# extruderControllerv02.net
KiCad netlist of a schematic drawn in EAGLE
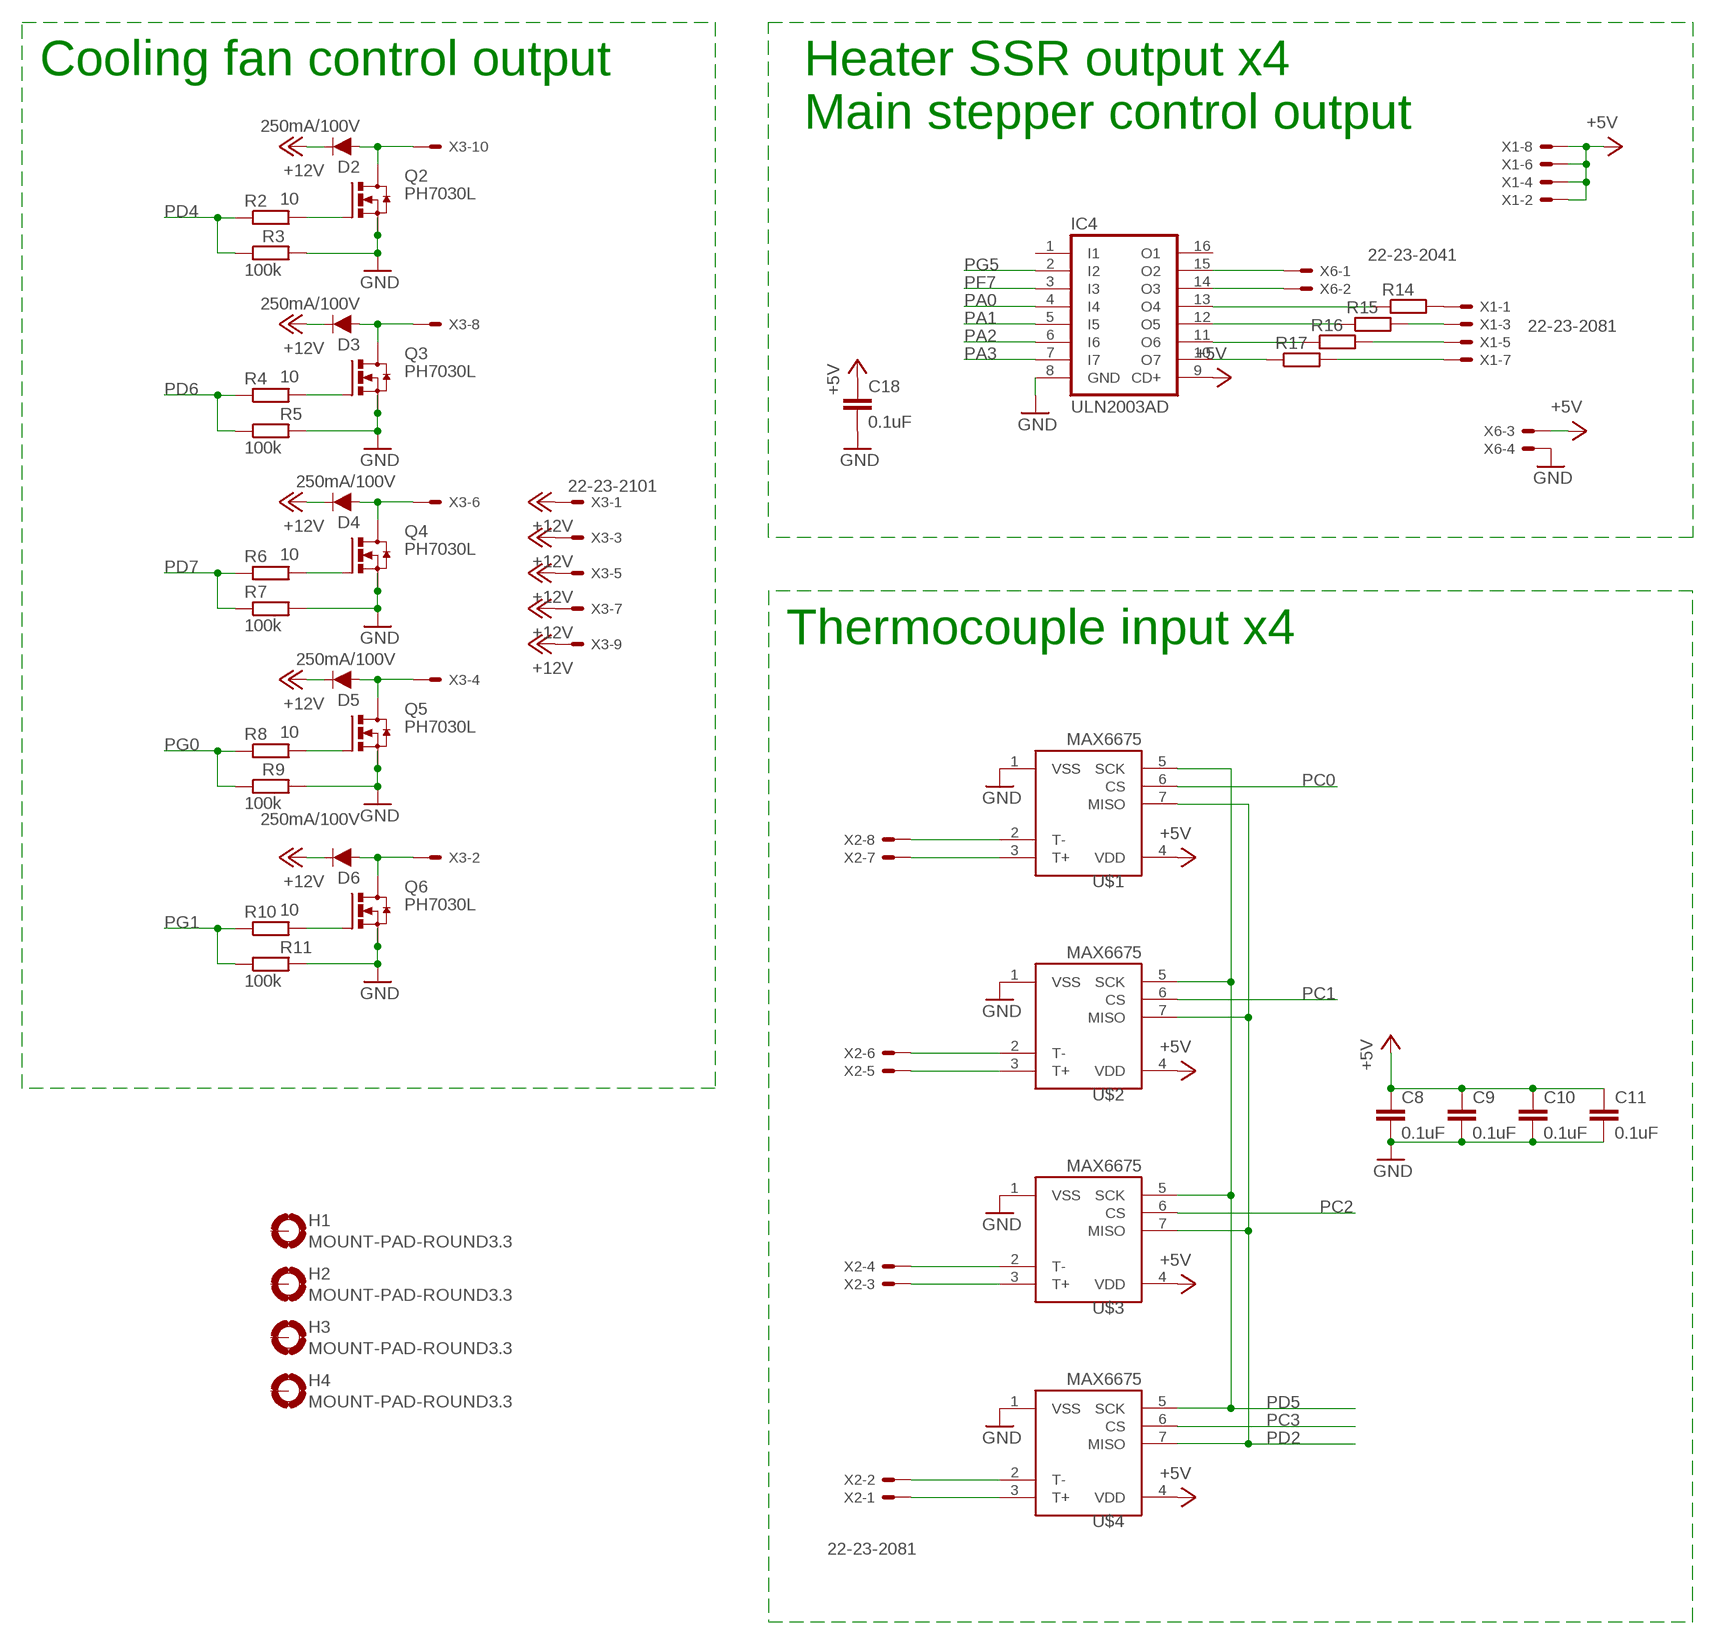
[diagram p0: schematic, sheet 1, part 1 of 2]
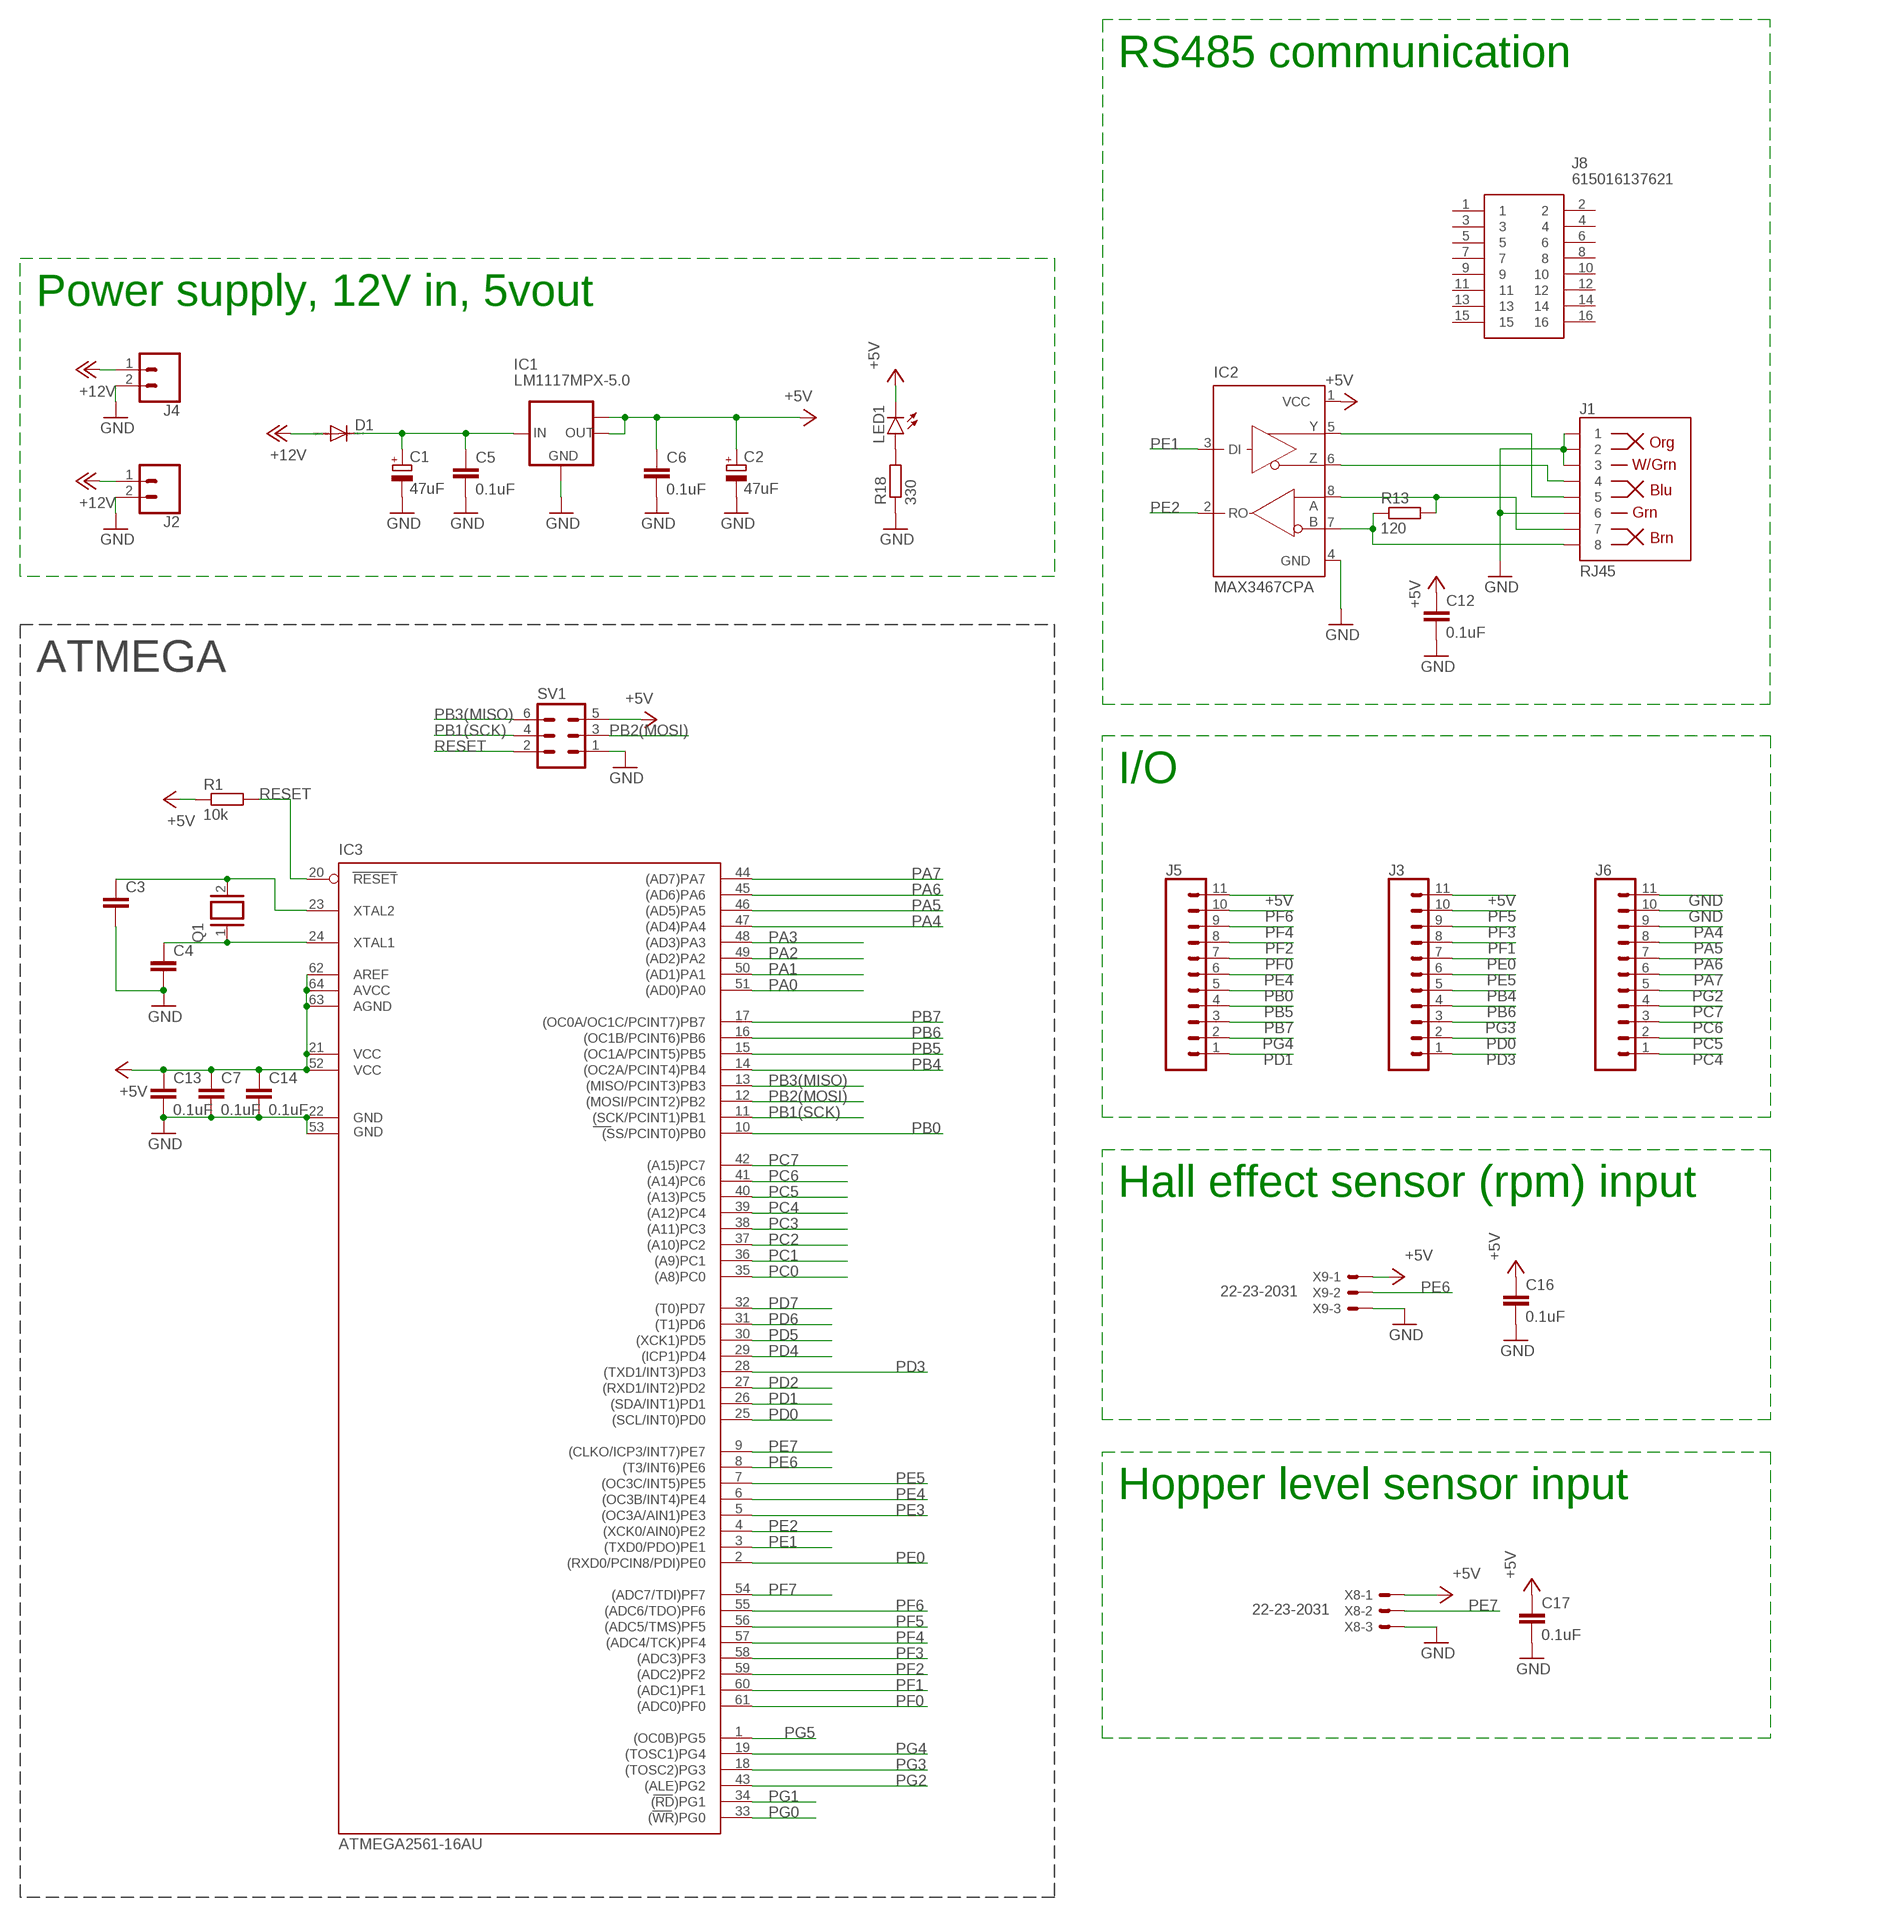
[diagram p1: schematic, sheet 1, part 2 of 2]

(export (version "E")
  (design (tool "Eeschema 10.0.6"))
  (components
    (comp (ref "C1")
      (value "47uF")
      (footprint "eagle-import:PANASONIC_D")
      (libsource (lib "eagle-import") (part "CPOL-EUD"))
    )
    (comp (ref "C2")
      (value "47uF")
      (footprint "eagle-import:PANASONIC_D")
      (libsource (lib "eagle-import") (part "CPOL-EUD"))
    )
    (comp (ref "C3")
      (value "C-EUC0603")
      (footprint "eagle-import:C0603")
      (libsource (lib "eagle-import") (part "C-EUC0603"))
    )
    (comp (ref "C4")
      (value "C-EUC0603")
      (footprint "eagle-import:C0603")
      (libsource (lib "eagle-import") (part "C-EUC0603"))
    )
    (comp (ref "C5")
      (value "0.1uF")
      (footprint "eagle-import:C0603")
      (libsource (lib "eagle-import") (part "C-EUC0603"))
    )
    (comp (ref "C6")
      (value "0.1uF")
      (footprint "eagle-import:C0603")
      (libsource (lib "eagle-import") (part "C-EUC0603"))
    )
    (comp (ref "C7")
      (value "0.1uF")
      (footprint "eagle-import:C0603")
      (libsource (lib "eagle-import") (part "C-EUC0603"))
    )
    (comp (ref "C8")
      (value "0.1uF")
      (footprint "eagle-import:C0603")
      (libsource (lib "eagle-import") (part "C-EUC0603"))
    )
    (comp (ref "C9")
      (value "0.1uF")
      (footprint "eagle-import:C0603")
      (libsource (lib "eagle-import") (part "C-EUC0603"))
    )
    (comp (ref "C10")
      (value "0.1uF")
      (footprint "eagle-import:C0603")
      (libsource (lib "eagle-import") (part "C-EUC0603"))
    )
    (comp (ref "C11")
      (value "0.1uF")
      (footprint "eagle-import:C0603")
      (libsource (lib "eagle-import") (part "C-EUC0603"))
    )
    (comp (ref "C12")
      (value "0.1uF")
      (footprint "eagle-import:C0603")
      (libsource (lib "eagle-import") (part "C-EUC0603"))
    )
    (comp (ref "C13")
      (value "0.1uF")
      (footprint "eagle-import:C0603")
      (libsource (lib "eagle-import") (part "C-EUC0603"))
    )
    (comp (ref "C14")
      (value "0.1uF")
      (footprint "eagle-import:C0603")
      (libsource (lib "eagle-import") (part "C-EUC0603"))
    )
    (comp (ref "C16")
      (value "0.1uF")
      (footprint "eagle-import:C0603")
      (libsource (lib "eagle-import") (part "C-EUC0603"))
    )
    (comp (ref "C17")
      (value "0.1uF")
      (footprint "eagle-import:C0603")
      (libsource (lib "eagle-import") (part "C-EUC0603"))
    )
    (comp (ref "C18")
      (value "0.1uF")
      (footprint "eagle-import:C0603")
      (libsource (lib "eagle-import") (part "C-EUC0603"))
    )
    (comp (ref "D1")
      (value "DIODE-SMB")
      (footprint "eagle-import:SMB")
      (libsource (lib "eagle-import") (part "DIODE-SMB"))
    )
    (comp (ref "D2")
      (value "250mA/100V")
      (footprint "eagle-import:SOD-323")
      (libsource (lib "eagle-import") (part "DIODE-BAS16J"))
    )
    (comp (ref "D3")
      (value "250mA/100V")
      (footprint "eagle-import:SOD-323")
      (libsource (lib "eagle-import") (part "DIODE-BAS16J"))
    )
    (comp (ref "D4")
      (value "250mA/100V")
      (footprint "eagle-import:SOD-323")
      (libsource (lib "eagle-import") (part "DIODE-BAS16J"))
    )
    (comp (ref "D5")
      (value "250mA/100V")
      (footprint "eagle-import:SOD-323")
      (libsource (lib "eagle-import") (part "DIODE-BAS16J"))
    )
    (comp (ref "D6")
      (value "250mA/100V")
      (footprint "eagle-import:SOD-323")
      (libsource (lib "eagle-import") (part "DIODE-BAS16J"))
    )
    (comp (ref "H1")
      (value "MOUNT-PAD-ROUND3.3")
      (footprint "eagle-import:3,3-PAD")
      (libsource (lib "eagle-import") (part "MOUNT-PAD-ROUND3.3"))
    )
    (comp (ref "H2")
      (value "MOUNT-PAD-ROUND3.3")
      (footprint "eagle-import:3,3-PAD")
      (libsource (lib "eagle-import") (part "MOUNT-PAD-ROUND3.3"))
    )
    (comp (ref "H3")
      (value "MOUNT-PAD-ROUND3.3")
      (footprint "eagle-import:3,3-PAD")
      (libsource (lib "eagle-import") (part "MOUNT-PAD-ROUND3.3"))
    )
    (comp (ref "H4")
      (value "MOUNT-PAD-ROUND3.3")
      (footprint "eagle-import:3,3-PAD")
      (libsource (lib "eagle-import") (part "MOUNT-PAD-ROUND3.3"))
    )
    (comp (ref "IC1")
      (value "LM1117MPX-5.0")
      (footprint "eagle-import:SOT223")
      (libsource (lib "eagle-import") (part "LM1117MPX-5.0"))
    )
    (comp (ref "IC2")
      (value "MAX3467CPA")
      (footprint "eagle-import:SO08")
      (libsource (lib "eagle-import") (part "MAX3467PAC"))
    )
    (comp (ref "IC3")
      (value "ATMEGA2561-16AU")
      (footprint "eagle-import:TQFP64")
      (libsource (lib "eagle-import") (part "ATMEGA2561AU-16"))
    )
    (comp (ref "IC4")
      (value "ULN2003AD")
      (footprint "eagle-import:SO16")
      (libsource (lib "eagle-import") (part "ULN2003AD"))
    )
    (comp (ref "J1")
      (value "RJ45")
      (footprint "eagle-import:RJ45-8")
      (libsource (lib "eagle-import") (part "RJ45-8"))
    )
    (comp (ref "J2")
      (value "CONN_023.5MM")
      (footprint "eagle-import:SCREWTERMINAL-3.5MM-2")
      (libsource (lib "eagle-import") (part "CONN_023.5MM"))
    )
    (comp (ref "J3")
      (value "CONN_11")
      (footprint "eagle-import:1X11")
      (libsource (lib "eagle-import") (part "CONN_11"))
    )
    (comp (ref "J4")
      (value "CONN_023.5MM")
      (footprint "eagle-import:SCREWTERMINAL-3.5MM-2")
      (libsource (lib "eagle-import") (part "CONN_023.5MM"))
    )
    (comp (ref "J5")
      (value "CONN_11")
      (footprint "eagle-import:1X11")
      (libsource (lib "eagle-import") (part "CONN_11"))
    )
    (comp (ref "J6")
      (value "CONN_11")
      (footprint "eagle-import:1X11")
      (libsource (lib "eagle-import") (part "CONN_11"))
    )
    (comp (ref "J8")
      (value "615016137621")
      (footprint "eagle-import:WR-MJ")
      (fields (field (name "MOUSER_PART_NUMBER") "710-615016137621"))
      (libsource (lib "eagle-import") (part "615016137621"))
    )
    (comp (ref "LED1")
      (value "LEDSML1206")
      (footprint "eagle-import:SML1206")
      (libsource (lib "eagle-import") (part "LEDSML1206"))
    )
    (comp (ref "Q1")
      (value "XTAL/S")
      (footprint "eagle-import:QS")
      (fields (field (name "SPICEPREFIX") "B"))
      (libsource (lib "eagle-import") (part "XTAL/S"))
    )
    (comp (ref "Q2")
      (value "PH7030L")
      (footprint "eagle-import:SOT669")
      (libsource (lib "eagle-import") (part "PH7030L"))
    )
    (comp (ref "Q3")
      (value "PH7030L")
      (footprint "eagle-import:SOT669")
      (libsource (lib "eagle-import") (part "PH7030L"))
    )
    (comp (ref "Q4")
      (value "PH7030L")
      (footprint "eagle-import:SOT669")
      (libsource (lib "eagle-import") (part "PH7030L"))
    )
    (comp (ref "Q5")
      (value "PH7030L")
      (footprint "eagle-import:SOT669")
      (libsource (lib "eagle-import") (part "PH7030L"))
    )
    (comp (ref "Q6")
      (value "PH7030L")
      (footprint "eagle-import:SOT669")
      (libsource (lib "eagle-import") (part "PH7030L"))
    )
    (comp (ref "R1")
      (value "10k")
      (footprint "eagle-import:R0805")
      (libsource (lib "eagle-import") (part "R-EU_R0805"))
    )
    (comp (ref "R2")
      (value "10")
      (footprint "eagle-import:R0805")
      (libsource (lib "eagle-import") (part "R-EU_R0805"))
    )
    (comp (ref "R3")
      (value "100k")
      (footprint "eagle-import:R0805")
      (libsource (lib "eagle-import") (part "R-EU_R0805"))
    )
    (comp (ref "R4")
      (value "10")
      (footprint "eagle-import:R0805")
      (libsource (lib "eagle-import") (part "R-EU_R0805"))
    )
    (comp (ref "R5")
      (value "100k")
      (footprint "eagle-import:R0805")
      (libsource (lib "eagle-import") (part "R-EU_R0805"))
    )
    (comp (ref "R6")
      (value "10")
      (footprint "eagle-import:R0805")
      (libsource (lib "eagle-import") (part "R-EU_R0805"))
    )
    (comp (ref "R7")
      (value "100k")
      (footprint "eagle-import:R0805")
      (libsource (lib "eagle-import") (part "R-EU_R0805"))
    )
    (comp (ref "R8")
      (value "10")
      (footprint "eagle-import:R0805")
      (libsource (lib "eagle-import") (part "R-EU_R0805"))
    )
    (comp (ref "R9")
      (value "100k")
      (footprint "eagle-import:R0805")
      (libsource (lib "eagle-import") (part "R-EU_R0805"))
    )
    (comp (ref "R10")
      (value "10")
      (footprint "eagle-import:R0805")
      (libsource (lib "eagle-import") (part "R-EU_R0805"))
    )
    (comp (ref "R11")
      (value "100k")
      (footprint "eagle-import:R0805")
      (libsource (lib "eagle-import") (part "R-EU_R0805"))
    )
    (comp (ref "R13")
      (value "120")
      (footprint "eagle-import:R1210")
      (libsource (lib "eagle-import") (part "R-EU_R1210"))
    )
    (comp (ref "R14")
      (value "R-EU_R0805")
      (footprint "eagle-import:R0805")
      (libsource (lib "eagle-import") (part "R-EU_R0805"))
    )
    (comp (ref "R15")
      (value "R-EU_R0805")
      (footprint "eagle-import:R0805")
      (libsource (lib "eagle-import") (part "R-EU_R0805"))
    )
    (comp (ref "R16")
      (value "R-EU_R0805")
      (footprint "eagle-import:R0805")
      (libsource (lib "eagle-import") (part "R-EU_R0805"))
    )
    (comp (ref "R17")
      (value "R-EU_R0805")
      (footprint "eagle-import:R0805")
      (libsource (lib "eagle-import") (part "R-EU_R0805"))
    )
    (comp (ref "R18")
      (value "330")
      (footprint "eagle-import:R0805")
      (libsource (lib "eagle-import") (part "R-EU_R0805"))
    )
    (comp (ref "SV1")
      (value "MA03-2")
      (footprint "eagle-import:MA03-2")
      (libsource (lib "eagle-import") (part "MA03-2"))
    )
    (comp (ref "U$1")
      (value "MAX6675")
      (footprint "eagle-import:SO08-MAX6675")
      (libsource (lib "eagle-import") (part "MAX6675"))
    )
    (comp (ref "U$2")
      (value "MAX6675")
      (footprint "eagle-import:SO08-MAX6675")
      (libsource (lib "eagle-import") (part "MAX6675"))
    )
    (comp (ref "U$3")
      (value "MAX6675")
      (footprint "eagle-import:SO08-MAX6675")
      (libsource (lib "eagle-import") (part "MAX6675"))
    )
    (comp (ref "U$4")
      (value "MAX6675")
      (footprint "eagle-import:SO08-MAX6675")
      (libsource (lib "eagle-import") (part "MAX6675"))
    )
    (comp (ref "X1")
      (value "22-23-2081")
      (footprint "eagle-import:22-23-2081")
      (fields (field (name "MF") "MOLEX"))
      (libsource (lib "eagle-import") (part "22-23-2081"))
    )
    (comp (ref "X2")
      (value "22-23-2081")
      (footprint "eagle-import:22-23-2081")
      (fields (field (name "MF") "MOLEX"))
      (libsource (lib "eagle-import") (part "22-23-2081"))
    )
    (comp (ref "X3")
      (value "22-23-2101")
      (footprint "eagle-import:22-23-2101")
      (fields (field (name "MF") "MOLEX"))
      (libsource (lib "eagle-import") (part "22-23-2101"))
    )
    (comp (ref "X6")
      (value "22-23-2041")
      (footprint "eagle-import:22-23-2041")
      (fields (field (name "MF") "MOLEX"))
      (libsource (lib "eagle-import") (part "22-23-2041"))
    )
    (comp (ref "X8")
      (value "22-23-2031")
      (footprint "eagle-import:22-23-2031")
      (fields (field (name "MF") "MOLEX"))
      (libsource (lib "eagle-import") (part "22-23-2031"))
    )
    (comp (ref "X9")
      (value "22-23-2031")
      (footprint "eagle-import:22-23-2031")
      (fields (field (name "MF") "MOLEX"))
      (libsource (lib "eagle-import") (part "22-23-2031"))
    )
  )
  (nets
    (net (code "1") (name "+5V") (class "Default")
      (node (ref "C10") (pin "1") (pinfunction "1_1") (pintype "passive"))
      (node (ref "C11") (pin "1") (pinfunction "1_1") (pintype "passive"))
      (node (ref "C12") (pin "1") (pinfunction "1_1") (pintype "passive"))
      (node (ref "C13") (pin "1") (pinfunction "1_1") (pintype "passive"))
      (node (ref "C14") (pin "1") (pinfunction "1_1") (pintype "passive"))
      (node (ref "C16") (pin "1") (pinfunction "1_1") (pintype "passive"))
      (node (ref "C17") (pin "1") (pinfunction "1_1") (pintype "passive"))
      (node (ref "C18") (pin "1") (pinfunction "1_1") (pintype "passive"))
      (node (ref "C2") (pin "+") (pinfunction "+_+") (pintype "passive"))
      (node (ref "C6") (pin "1") (pinfunction "1_1") (pintype "passive"))
      (node (ref "C7") (pin "1") (pinfunction "1_1") (pintype "passive"))
      (node (ref "C8") (pin "1") (pinfunction "1_1") (pintype "passive"))
      (node (ref "C9") (pin "1") (pinfunction "1_1") (pintype "passive"))
      (node (ref "IC1") (pin "2") (pinfunction "OUT_2") (pintype "passive"))
      (node (ref "IC1") (pin "TAB") (pinfunction "OUT1_TAB") (pintype "passive"))
      (node (ref "IC2") (pin "1") (pinfunction "VCC_1") (pintype "power_in"))
      (node (ref "IC3") (pin "21") (pinfunction "VCC_21") (pintype "power_in"))
      (node (ref "IC3") (pin "52") (pinfunction "VCC1_52") (pintype "power_in"))
      (node (ref "IC3") (pin "62") (pinfunction "AREF_62") (pintype "bidirectional"))
      (node (ref "IC3") (pin "63") (pinfunction "AGND_63") (pintype "power_in"))
      (node (ref "IC3") (pin "64") (pinfunction "AVCC_64") (pintype "power_in"))
      (node (ref "IC4") (pin "9") (pinfunction "CD+_9") (pintype "passive"))
      (node (ref "J3") (pin "11") (pinfunction "11_11") (pintype "passive"))
      (node (ref "J5") (pin "11") (pinfunction "11_11") (pintype "passive"))
      (node (ref "LED1") (pin "C") (pinfunction "C_C") (pintype "passive"))
      (node (ref "R1") (pin "1") (pinfunction "1_1") (pintype "passive"))
      (node (ref "SV1") (pin "5") (pinfunction "5_5") (pintype "passive"))
      (node (ref "U$1") (pin "4") (pinfunction "VDD_4") (pintype "bidirectional"))
      (node (ref "U$2") (pin "4") (pinfunction "VDD_4") (pintype "bidirectional"))
      (node (ref "U$3") (pin "4") (pinfunction "VDD_4") (pintype "bidirectional"))
      (node (ref "U$4") (pin "4") (pinfunction "VDD_4") (pintype "bidirectional"))
      (node (ref "X1") (pin "2") (pinfunction "S_2") (pintype "passive"))
      (node (ref "X1") (pin "4") (pinfunction "S_4") (pintype "passive"))
      (node (ref "X1") (pin "6") (pinfunction "S_6") (pintype "passive"))
      (node (ref "X1") (pin "8") (pinfunction "S_8") (pintype "passive"))
      (node (ref "X6") (pin "3") (pinfunction "S_3") (pintype "passive"))
      (node (ref "X8") (pin "1") (pinfunction "S_1") (pintype "passive"))
      (node (ref "X9") (pin "1") (pinfunction "S_1") (pintype "passive"))
    )
    (net (code "2") (name "+12V") (class "Default")
      (node (ref "D1") (pin "A") (pinfunction "A_A") (pintype "passive"))
      (node (ref "D2") (pin "C") (pinfunction "C_C") (pintype "passive"))
      (node (ref "D3") (pin "C") (pinfunction "C_C") (pintype "passive"))
      (node (ref "D4") (pin "C") (pinfunction "C_C") (pintype "passive"))
      (node (ref "D5") (pin "C") (pinfunction "C_C") (pintype "passive"))
      (node (ref "D6") (pin "C") (pinfunction "C_C") (pintype "passive"))
      (node (ref "J2") (pin "1") (pinfunction "1_1") (pintype "passive"))
      (node (ref "J4") (pin "1") (pinfunction "1_1") (pintype "passive"))
      (node (ref "X3") (pin "1") (pinfunction "S_1") (pintype "passive"))
      (node (ref "X3") (pin "3") (pinfunction "S_3") (pintype "passive"))
      (node (ref "X3") (pin "5") (pinfunction "S_5") (pintype "passive"))
      (node (ref "X3") (pin "7") (pinfunction "S_7") (pintype "passive"))
      (node (ref "X3") (pin "9") (pinfunction "S_9") (pintype "passive"))
    )
    (net (code "3") (name "/PA0") (class "Default")
      (node (ref "IC3") (pin "51") (pinfunction "(AD0)PA0_51") (pintype "bidirectional"))
      (node (ref "IC4") (pin "4") (pinfunction "I4_4") (pintype "input"))
    )
    (net (code "4") (name "/PA1") (class "Default")
      (node (ref "IC3") (pin "50") (pinfunction "(AD1)PA1_50") (pintype "bidirectional"))
      (node (ref "IC4") (pin "5") (pinfunction "I5_5") (pintype "input"))
    )
    (net (code "5") (name "/PA2") (class "Default")
      (node (ref "IC3") (pin "49") (pinfunction "(AD2)PA2_49") (pintype "bidirectional"))
      (node (ref "IC4") (pin "6") (pinfunction "I6_6") (pintype "input"))
    )
    (net (code "6") (name "/PA3") (class "Default")
      (node (ref "IC3") (pin "48") (pinfunction "(AD3)PA3_48") (pintype "bidirectional"))
      (node (ref "IC4") (pin "7") (pinfunction "I7_7") (pintype "input"))
    )
    (net (code "7") (name "/PA4") (class "Default")
      (node (ref "IC3") (pin "47") (pinfunction "(AD4)PA4_47") (pintype "bidirectional"))
      (node (ref "J6") (pin "9") (pinfunction "9_9") (pintype "passive"))
    )
    (net (code "8") (name "/PA5") (class "Default")
      (node (ref "IC3") (pin "46") (pinfunction "(AD5)PA5_46") (pintype "bidirectional"))
      (node (ref "J6") (pin "8") (pinfunction "8_8") (pintype "passive"))
    )
    (net (code "9") (name "/PA6") (class "Default")
      (node (ref "IC3") (pin "45") (pinfunction "(AD6)PA6_45") (pintype "bidirectional"))
      (node (ref "J6") (pin "7") (pinfunction "7_7") (pintype "passive"))
    )
    (net (code "10") (name "/PA7") (class "Default")
      (node (ref "IC3") (pin "44") (pinfunction "(AD7)PA7_44") (pintype "bidirectional"))
      (node (ref "J6") (pin "6") (pinfunction "6_6") (pintype "passive"))
    )
    (net (code "11") (name "/PB0") (class "Default")
      (node (ref "IC3") (pin "10") (pinfunction "(SS/PCINT0)PB0_10") (pintype "bidirectional"))
      (node (ref "J5") (pin "5") (pinfunction "5_5") (pintype "passive"))
    )
    (net (code "12") (name "/PB1(SCK)") (class "Default")
      (node (ref "IC3") (pin "11") (pinfunction "(SCK/PCINT1)PB1_11") (pintype "bidirectional"))
      (node (ref "SV1") (pin "4") (pinfunction "4_4") (pintype "passive"))
    )
    (net (code "13") (name "/PB2(MOSI)") (class "Default")
      (node (ref "IC3") (pin "12") (pinfunction "(MOSI/PCINT2)PB2_12") (pintype "bidirectional"))
      (node (ref "SV1") (pin "3") (pinfunction "3_3") (pintype "passive"))
    )
    (net (code "14") (name "/PB3(MISO)") (class "Default")
      (node (ref "IC3") (pin "13") (pinfunction "(MISO/PCINT3)PB3_13") (pintype "bidirectional"))
      (node (ref "SV1") (pin "6") (pinfunction "6_6") (pintype "passive"))
    )
    (net (code "15") (name "/PB4") (class "Default")
      (node (ref "IC3") (pin "14") (pinfunction "(OC2A/PCINT4)PB4_14") (pintype "bidirectional"))
      (node (ref "J3") (pin "5") (pinfunction "5_5") (pintype "passive"))
    )
    (net (code "16") (name "/PB5") (class "Default")
      (node (ref "IC3") (pin "15") (pinfunction "(OC1A/PCINT5)PB5_15") (pintype "bidirectional"))
      (node (ref "J5") (pin "4") (pinfunction "4_4") (pintype "passive"))
    )
    (net (code "17") (name "/PB6") (class "Default")
      (node (ref "IC3") (pin "16") (pinfunction "(OC1B/PCINT6)PB6_16") (pintype "bidirectional"))
      (node (ref "J3") (pin "4") (pinfunction "4_4") (pintype "passive"))
    )
    (net (code "18") (name "/PB7") (class "Default")
      (node (ref "IC3") (pin "17") (pinfunction "(OC0A/OC1C/PCINT7)PB7_17") (pintype "bidirectional"))
      (node (ref "J5") (pin "3") (pinfunction "3_3") (pintype "passive"))
    )
    (net (code "19") (name "/PC0") (class "Default")
      (node (ref "IC3") (pin "35") (pinfunction "(A8)PC0_35") (pintype "bidirectional"))
      (node (ref "U$1") (pin "6") (pinfunction "CS_6") (pintype "bidirectional"))
    )
    (net (code "20") (name "/PC1") (class "Default")
      (node (ref "IC3") (pin "36") (pinfunction "(A9)PC1_36") (pintype "bidirectional"))
      (node (ref "U$2") (pin "6") (pinfunction "CS_6") (pintype "bidirectional"))
    )
    (net (code "21") (name "/PC2") (class "Default")
      (node (ref "IC3") (pin "37") (pinfunction "(A10)PC2_37") (pintype "bidirectional"))
      (node (ref "U$3") (pin "6") (pinfunction "CS_6") (pintype "bidirectional"))
    )
    (net (code "22") (name "/PC3") (class "Default")
      (node (ref "IC3") (pin "38") (pinfunction "(A11)PC3_38") (pintype "bidirectional"))
      (node (ref "U$4") (pin "6") (pinfunction "CS_6") (pintype "bidirectional"))
    )
    (net (code "23") (name "/PC4") (class "Default")
      (node (ref "IC3") (pin "39") (pinfunction "(A12)PC4_39") (pintype "bidirectional"))
      (node (ref "J6") (pin "1") (pinfunction "1_1") (pintype "passive"))
    )
    (net (code "24") (name "/PC5") (class "Default")
      (node (ref "IC3") (pin "40") (pinfunction "(A13)PC5_40") (pintype "bidirectional"))
      (node (ref "J6") (pin "2") (pinfunction "2_2") (pintype "passive"))
    )
    (net (code "25") (name "/PC6") (class "Default")
      (node (ref "IC3") (pin "41") (pinfunction "(A14)PC6_41") (pintype "bidirectional"))
      (node (ref "J6") (pin "3") (pinfunction "3_3") (pintype "passive"))
    )
    (net (code "26") (name "/PC7") (class "Default")
      (node (ref "IC3") (pin "42") (pinfunction "(A15)PC7_42") (pintype "bidirectional"))
      (node (ref "J6") (pin "4") (pinfunction "4_4") (pintype "passive"))
    )
    (net (code "27") (name "/PD0") (class "Default")
      (node (ref "IC3") (pin "25") (pinfunction "(SCL/INT0)PD0_25") (pintype "bidirectional"))
      (node (ref "J3") (pin "2") (pinfunction "2_2") (pintype "passive"))
    )
    (net (code "28") (name "/PD1") (class "Default")
      (node (ref "IC3") (pin "26") (pinfunction "(SDA/INT1)PD1_26") (pintype "bidirectional"))
      (node (ref "J5") (pin "1") (pinfunction "1_1") (pintype "passive"))
    )
    (net (code "29") (name "/PD2") (class "Default")
      (node (ref "IC3") (pin "27") (pinfunction "(RXD1/INT2)PD2_27") (pintype "bidirectional"))
      (node (ref "U$1") (pin "7") (pinfunction "MISO_7") (pintype "bidirectional"))
      (node (ref "U$2") (pin "7") (pinfunction "MISO_7") (pintype "bidirectional"))
      (node (ref "U$3") (pin "7") (pinfunction "MISO_7") (pintype "bidirectional"))
      (node (ref "U$4") (pin "7") (pinfunction "MISO_7") (pintype "bidirectional"))
    )
    (net (code "30") (name "/PD3") (class "Default")
      (node (ref "IC3") (pin "28") (pinfunction "(TXD1/INT3)PD3_28") (pintype "bidirectional"))
      (node (ref "J3") (pin "1") (pinfunction "1_1") (pintype "passive"))
    )
    (net (code "31") (name "/PD4") (class "Default")
      (node (ref "IC3") (pin "29") (pinfunction "(ICP1)PD4_29") (pintype "bidirectional"))
      (node (ref "R2") (pin "1") (pinfunction "1_1") (pintype "passive"))
      (node (ref "R3") (pin "1") (pinfunction "1_1") (pintype "passive"))
    )
    (net (code "32") (name "/PD5") (class "Default")
      (node (ref "IC3") (pin "30") (pinfunction "(XCK1)PD5_30") (pintype "bidirectional"))
      (node (ref "U$1") (pin "5") (pinfunction "SCK_5") (pintype "bidirectional"))
      (node (ref "U$2") (pin "5") (pinfunction "SCK_5") (pintype "bidirectional"))
      (node (ref "U$3") (pin "5") (pinfunction "SCK_5") (pintype "bidirectional"))
      (node (ref "U$4") (pin "5") (pinfunction "SCK_5") (pintype "bidirectional"))
    )
    (net (code "33") (name "/PD6") (class "Default")
      (node (ref "IC3") (pin "31") (pinfunction "(T1)PD6_31") (pintype "bidirectional"))
      (node (ref "R4") (pin "1") (pinfunction "1_1") (pintype "passive"))
      (node (ref "R5") (pin "1") (pinfunction "1_1") (pintype "passive"))
    )
    (net (code "34") (name "/PD7") (class "Default")
      (node (ref "IC3") (pin "32") (pinfunction "(T0)PD7_32") (pintype "bidirectional"))
      (node (ref "R6") (pin "1") (pinfunction "1_1") (pintype "passive"))
      (node (ref "R7") (pin "1") (pinfunction "1_1") (pintype "passive"))
    )
    (net (code "35") (name "/PE0") (class "Default")
      (node (ref "IC3") (pin "2") (pinfunction "(RXD0/PCIN8/PDI)PE0_2") (pintype "bidirectional"))
      (node (ref "J3") (pin "7") (pinfunction "7_7") (pintype "passive"))
    )
    (net (code "36") (name "/PE1") (class "Default")
      (node (ref "IC2") (pin "3") (pinfunction "DI_3") (pintype "input"))
      (node (ref "IC3") (pin "3") (pinfunction "(TXD0/PDO)PE1_3") (pintype "bidirectional"))
    )
    (net (code "37") (name "/PE2") (class "Default")
      (node (ref "IC2") (pin "2") (pinfunction "RO_2") (pintype "output"))
      (node (ref "IC3") (pin "4") (pinfunction "(XCK0/AIN0)PE2_4") (pintype "bidirectional"))
    )
    (net (code "38") (name "/PE3") (class "Default")
      (node (ref "IC3") (pin "5") (pinfunction "(OC3A/AIN1)PE3_5") (pintype "bidirectional"))
    )
    (net (code "39") (name "/PE4") (class "Default")
      (node (ref "IC3") (pin "6") (pinfunction "(OC3B/INT4)PE4_6") (pintype "bidirectional"))
      (node (ref "J5") (pin "6") (pinfunction "6_6") (pintype "passive"))
    )
    (net (code "40") (name "/PE5") (class "Default")
      (node (ref "IC3") (pin "7") (pinfunction "(OC3C/INT5)PE5_7") (pintype "bidirectional"))
      (node (ref "J3") (pin "6") (pinfunction "6_6") (pintype "passive"))
    )
    (net (code "41") (name "/PE6") (class "Default")
      (node (ref "IC3") (pin "8") (pinfunction "(T3/INT6)PE6_8") (pintype "bidirectional"))
      (node (ref "X9") (pin "2") (pinfunction "S_2") (pintype "passive"))
    )
    (net (code "42") (name "/PE7") (class "Default")
      (node (ref "IC3") (pin "9") (pinfunction "(CLKO/ICP3/INT7)PE7_9") (pintype "bidirectional"))
      (node (ref "X8") (pin "2") (pinfunction "S_2") (pintype "passive"))
    )
    (net (code "43") (name "/PF0") (class "Default")
      (node (ref "IC3") (pin "61") (pinfunction "(ADC0)PF0_61") (pintype "bidirectional"))
      (node (ref "J5") (pin "7") (pinfunction "7_7") (pintype "passive"))
    )
    (net (code "44") (name "/PF1") (class "Default")
      (node (ref "IC3") (pin "60") (pinfunction "(ADC1)PF1_60") (pintype "bidirectional"))
      (node (ref "J3") (pin "8") (pinfunction "8_8") (pintype "passive"))
    )
    (net (code "45") (name "/PF2") (class "Default")
      (node (ref "IC3") (pin "59") (pinfunction "(ADC2)PF2_59") (pintype "bidirectional"))
      (node (ref "J5") (pin "8") (pinfunction "8_8") (pintype "passive"))
    )
    (net (code "46") (name "/PF3") (class "Default")
      (node (ref "IC3") (pin "58") (pinfunction "(ADC3)PF3_58") (pintype "bidirectional"))
      (node (ref "J3") (pin "9") (pinfunction "9_9") (pintype "passive"))
    )
    (net (code "47") (name "/PF4") (class "Default")
      (node (ref "IC3") (pin "57") (pinfunction "(ADC4/TCK)PF4_57") (pintype "bidirectional"))
      (node (ref "J5") (pin "9") (pinfunction "9_9") (pintype "passive"))
    )
    (net (code "48") (name "/PF5") (class "Default")
      (node (ref "IC3") (pin "56") (pinfunction "(ADC5/TMS)PF5_56") (pintype "bidirectional"))
      (node (ref "J3") (pin "10") (pinfunction "10_10") (pintype "passive"))
    )
    (net (code "49") (name "/PF6") (class "Default")
      (node (ref "IC3") (pin "55") (pinfunction "(ADC6/TDO)PF6_55") (pintype "bidirectional"))
      (node (ref "J5") (pin "10") (pinfunction "10_10") (pintype "passive"))
    )
    (net (code "50") (name "/PF7") (class "Default")
      (node (ref "IC3") (pin "54") (pinfunction "(ADC7/TDI)PF7_54") (pintype "bidirectional"))
      (node (ref "IC4") (pin "3") (pinfunction "I3_3") (pintype "input"))
    )
    (net (code "51") (name "/PG0") (class "Default")
      (node (ref "IC3") (pin "33") (pinfunction "(WR)PG0_33") (pintype "bidirectional"))
      (node (ref "R8") (pin "1") (pinfunction "1_1") (pintype "passive"))
      (node (ref "R9") (pin "1") (pinfunction "1_1") (pintype "passive"))
    )
    (net (code "52") (name "/PG1") (class "Default")
      (node (ref "IC3") (pin "34") (pinfunction "(RD)PG1_34") (pintype "bidirectional"))
      (node (ref "R10") (pin "1") (pinfunction "1_1") (pintype "passive"))
      (node (ref "R11") (pin "1") (pinfunction "1_1") (pintype "passive"))
    )
    (net (code "53") (name "/PG2") (class "Default")
      (node (ref "IC3") (pin "43") (pinfunction "(ALE)PG2_43") (pintype "bidirectional"))
      (node (ref "J6") (pin "5") (pinfunction "5_5") (pintype "passive"))
    )
    (net (code "54") (name "/PG3") (class "Default")
      (node (ref "IC3") (pin "18") (pinfunction "(TOSC2)PG3_18") (pintype "bidirectional"))
      (node (ref "J3") (pin "3") (pinfunction "3_3") (pintype "passive"))
    )
    (net (code "55") (name "/PG4") (class "Default")
      (node (ref "IC3") (pin "19") (pinfunction "(TOSC1)PG4_19") (pintype "bidirectional"))
      (node (ref "J5") (pin "2") (pinfunction "2_2") (pintype "passive"))
    )
    (net (code "56") (name "/PG5") (class "Default")
      (node (ref "IC3") (pin "1") (pinfunction "(OC0B)PG5_1") (pintype "bidirectional"))
      (node (ref "IC4") (pin "2") (pinfunction "I2_2") (pintype "input"))
    )
    (net (code "57") (name "/RESET") (class "Default")
      (node (ref "IC3") (pin "20") (pinfunction "RESET_20") (pintype "input"))
      (node (ref "R1") (pin "2") (pinfunction "2_2") (pintype "passive"))
      (node (ref "SV1") (pin "2") (pinfunction "2_2") (pintype "passive"))
    )
    (net (code "58") (name "GND") (class "Default")
      (node (ref "C1") (pin "-") (pinfunction "-_-") (pintype "passive"))
      (node (ref "C10") (pin "2") (pinfunction "2_2") (pintype "passive"))
      (node (ref "C11") (pin "2") (pinfunction "2_2") (pintype "passive"))
      (node (ref "C12") (pin "2") (pinfunction "2_2") (pintype "passive"))
      (node (ref "C13") (pin "2") (pinfunction "2_2") (pintype "passive"))
      (node (ref "C14") (pin "2") (pinfunction "2_2") (pintype "passive"))
      (node (ref "C16") (pin "2") (pinfunction "2_2") (pintype "passive"))
      (node (ref "C17") (pin "2") (pinfunction "2_2") (pintype "passive"))
      (node (ref "C18") (pin "2") (pinfunction "2_2") (pintype "passive"))
      (node (ref "C2") (pin "-") (pinfunction "-_-") (pintype "passive"))
      (node (ref "C3") (pin "2") (pinfunction "2_2") (pintype "passive"))
      (node (ref "C4") (pin "2") (pinfunction "2_2") (pintype "passive"))
      (node (ref "C5") (pin "2") (pinfunction "2_2") (pintype "passive"))
      (node (ref "C6") (pin "2") (pinfunction "2_2") (pintype "passive"))
      (node (ref "C7") (pin "2") (pinfunction "2_2") (pintype "passive"))
      (node (ref "C8") (pin "2") (pinfunction "2_2") (pintype "passive"))
      (node (ref "C9") (pin "2") (pinfunction "2_2") (pintype "passive"))
      (node (ref "IC1") (pin "1") (pinfunction "GND_1") (pintype "input"))
      (node (ref "IC2") (pin "4") (pinfunction "GND_4") (pintype "power_in"))
      (node (ref "IC3") (pin "22") (pinfunction "GND_22") (pintype "power_in"))
      (node (ref "IC3") (pin "53") (pinfunction "GND1_53") (pintype "power_in"))
      (node (ref "IC4") (pin "8") (pinfunction "GND_8") (pintype "power_in"))
      (node (ref "J1") (pin "1") (pinfunction "1_1") (pintype "bidirectional"))
      (node (ref "J1") (pin "2") (pinfunction "2_2") (pintype "bidirectional"))
      (node (ref "J1") (pin "3") (pinfunction "3_3") (pintype "bidirectional"))
      (node (ref "J1") (pin "6") (pinfunction "6_6") (pintype "bidirectional"))
      (node (ref "J2") (pin "2") (pinfunction "2_2") (pintype "passive"))
      (node (ref "J4") (pin "2") (pinfunction "2_2") (pintype "passive"))
      (node (ref "J6") (pin "10") (pinfunction "10_10") (pintype "passive"))
      (node (ref "J6") (pin "11") (pinfunction "11_11") (pintype "passive"))
      (node (ref "Q2") (pin "1") (pinfunction "S_1") (pintype "passive"))
      (node (ref "Q2") (pin "2") (pinfunction "S_2") (pintype "passive"))
      (node (ref "Q2") (pin "3") (pinfunction "S_3") (pintype "passive"))
      (node (ref "Q3") (pin "1") (pinfunction "S_1") (pintype "passive"))
      (node (ref "Q3") (pin "2") (pinfunction "S_2") (pintype "passive"))
      (node (ref "Q3") (pin "3") (pinfunction "S_3") (pintype "passive"))
      (node (ref "Q4") (pin "1") (pinfunction "S_1") (pintype "passive"))
      (node (ref "Q4") (pin "2") (pinfunction "S_2") (pintype "passive"))
      (node (ref "Q4") (pin "3") (pinfunction "S_3") (pintype "passive"))
      (node (ref "Q5") (pin "1") (pinfunction "S_1") (pintype "passive"))
      (node (ref "Q5") (pin "2") (pinfunction "S_2") (pintype "passive"))
      (node (ref "Q5") (pin "3") (pinfunction "S_3") (pintype "passive"))
      (node (ref "Q6") (pin "1") (pinfunction "S_1") (pintype "passive"))
      (node (ref "Q6") (pin "2") (pinfunction "S_2") (pintype "passive"))
      (node (ref "Q6") (pin "3") (pinfunction "S_3") (pintype "passive"))
      (node (ref "R11") (pin "2") (pinfunction "2_2") (pintype "passive"))
      (node (ref "R18") (pin "1") (pinfunction "1_1") (pintype "passive"))
      (node (ref "R3") (pin "2") (pinfunction "2_2") (pintype "passive"))
      (node (ref "R5") (pin "2") (pinfunction "2_2") (pintype "passive"))
      (node (ref "R7") (pin "2") (pinfunction "2_2") (pintype "passive"))
      (node (ref "R9") (pin "2") (pinfunction "2_2") (pintype "passive"))
      (node (ref "SV1") (pin "1") (pinfunction "1_1") (pintype "passive"))
      (node (ref "U$1") (pin "1") (pinfunction "VSS_1") (pintype "bidirectional"))
      (node (ref "U$2") (pin "1") (pinfunction "VSS_1") (pintype "bidirectional"))
      (node (ref "U$3") (pin "1") (pinfunction "VSS_1") (pintype "bidirectional"))
      (node (ref "U$4") (pin "1") (pinfunction "VSS_1") (pintype "bidirectional"))
      (node (ref "X6") (pin "4") (pinfunction "S_4") (pintype "passive"))
      (node (ref "X8") (pin "3") (pinfunction "S_3") (pintype "passive"))
      (node (ref "X9") (pin "3") (pinfunction "S_3") (pintype "passive"))
    )
    (net (code "59") (name "Net-(IC1-IN)") (class "Default")
      (node (ref "C1") (pin "+") (pinfunction "+_+") (pintype "passive"))
      (node (ref "C5") (pin "1") (pinfunction "1_1") (pintype "passive"))
      (node (ref "D1") (pin "C") (pinfunction "C_C") (pintype "passive"))
      (node (ref "IC1") (pin "3") (pinfunction "IN_3") (pintype "input"))
    )
    (net (code "60") (name "Net-(IC2-A)") (class "Default")
      (node (ref "IC2") (pin "8") (pinfunction "A_8") (pintype "passive"))
      (node (ref "J1") (pin "7") (pinfunction "7_7") (pintype "bidirectional"))
      (node (ref "R13") (pin "2") (pinfunction "2_2") (pintype "passive"))
    )
    (net (code "61") (name "Net-(IC2-B)") (class "Default")
      (node (ref "IC2") (pin "7") (pinfunction "B_7") (pintype "passive"))
      (node (ref "J1") (pin "8") (pinfunction "8_8") (pintype "bidirectional"))
      (node (ref "R13") (pin "1") (pinfunction "1_1") (pintype "passive"))
    )
    (net (code "62") (name "Net-(IC2-Y)") (class "Default")
      (node (ref "IC2") (pin "5") (pinfunction "Y_5") (pintype "passive"))
      (node (ref "J1") (pin "5") (pinfunction "5_5") (pintype "bidirectional"))
    )
    (net (code "63") (name "Net-(IC2-Z)") (class "Default")
      (node (ref "IC2") (pin "6") (pinfunction "Z_6") (pintype "passive"))
      (node (ref "J1") (pin "4") (pinfunction "4_4") (pintype "bidirectional"))
    )
    (net (code "64") (name "Net-(IC3-XTAL1)") (class "Default")
      (node (ref "C4") (pin "1") (pinfunction "1_1") (pintype "passive"))
      (node (ref "IC3") (pin "24") (pinfunction "XTAL1_24") (pintype "input"))
      (node (ref "Q1") (pin "1") (pinfunction "1_1") (pintype "passive"))
    )
    (net (code "65") (name "Net-(IC3-XTAL2)") (class "Default")
      (node (ref "C3") (pin "1") (pinfunction "1_1") (pintype "passive"))
      (node (ref "IC3") (pin "23") (pinfunction "XTAL2_23") (pintype "output"))
      (node (ref "Q1") (pin "2") (pinfunction "2_2") (pintype "passive"))
    )
    (net (code "66") (name "Net-(IC4-O2)") (class "Default")
      (node (ref "IC4") (pin "15") (pinfunction "O2_15") (pintype "open_collector"))
      (node (ref "X6") (pin "1") (pinfunction "S_1") (pintype "passive"))
    )
    (net (code "67") (name "Net-(IC4-O3)") (class "Default")
      (node (ref "IC4") (pin "14") (pinfunction "O3_14") (pintype "open_collector"))
      (node (ref "X6") (pin "2") (pinfunction "S_2") (pintype "passive"))
    )
    (net (code "68") (name "Net-(IC4-O4)") (class "Default")
      (node (ref "IC4") (pin "13") (pinfunction "O4_13") (pintype "open_collector"))
      (node (ref "R14") (pin "1") (pinfunction "1_1") (pintype "passive"))
    )
    (net (code "69") (name "Net-(IC4-O5)") (class "Default")
      (node (ref "IC4") (pin "12") (pinfunction "O5_12") (pintype "open_collector"))
      (node (ref "R15") (pin "1") (pinfunction "1_1") (pintype "passive"))
    )
    (net (code "70") (name "Net-(IC4-O6)") (class "Default")
      (node (ref "IC4") (pin "11") (pinfunction "O6_11") (pintype "open_collector"))
      (node (ref "R16") (pin "1") (pinfunction "1_1") (pintype "passive"))
    )
    (net (code "71") (name "Net-(IC4-O7)") (class "Default")
      (node (ref "IC4") (pin "10") (pinfunction "O7_10") (pintype "open_collector"))
      (node (ref "R17") (pin "1") (pinfunction "1_1") (pintype "passive"))
    )
    (net (code "72") (name "Net-(LED1-PadA)") (class "Default")
      (node (ref "LED1") (pin "A") (pinfunction "A_A") (pintype "passive"))
      (node (ref "R18") (pin "2") (pinfunction "2_2") (pintype "passive"))
    )
    (net (code "73") (name "Net-(Q2-D)") (class "Default")
      (node (ref "D2") (pin "A") (pinfunction "A_A") (pintype "passive"))
      (node (ref "Q2") (pin "MB") (pinfunction "D_MB") (pintype "passive"))
      (node (ref "X3") (pin "10") (pinfunction "S_10") (pintype "passive"))
    )
    (net (code "74") (name "Net-(Q2-G)") (class "Default")
      (node (ref "Q2") (pin "4") (pinfunction "G_4") (pintype "passive"))
      (node (ref "R2") (pin "2") (pinfunction "2_2") (pintype "passive"))
    )
    (net (code "75") (name "Net-(Q3-D)") (class "Default")
      (node (ref "D3") (pin "A") (pinfunction "A_A") (pintype "passive"))
      (node (ref "Q3") (pin "MB") (pinfunction "D_MB") (pintype "passive"))
      (node (ref "X3") (pin "8") (pinfunction "S_8") (pintype "passive"))
    )
    (net (code "76") (name "Net-(Q3-G)") (class "Default")
      (node (ref "Q3") (pin "4") (pinfunction "G_4") (pintype "passive"))
      (node (ref "R4") (pin "2") (pinfunction "2_2") (pintype "passive"))
    )
    (net (code "77") (name "Net-(Q4-D)") (class "Default")
      (node (ref "D4") (pin "A") (pinfunction "A_A") (pintype "passive"))
      (node (ref "Q4") (pin "MB") (pinfunction "D_MB") (pintype "passive"))
      (node (ref "X3") (pin "6") (pinfunction "S_6") (pintype "passive"))
    )
    (net (code "78") (name "Net-(Q4-G)") (class "Default")
      (node (ref "Q4") (pin "4") (pinfunction "G_4") (pintype "passive"))
      (node (ref "R6") (pin "2") (pinfunction "2_2") (pintype "passive"))
    )
    (net (code "79") (name "Net-(Q5-D)") (class "Default")
      (node (ref "D5") (pin "A") (pinfunction "A_A") (pintype "passive"))
      (node (ref "Q5") (pin "MB") (pinfunction "D_MB") (pintype "passive"))
      (node (ref "X3") (pin "4") (pinfunction "S_4") (pintype "passive"))
    )
    (net (code "80") (name "Net-(Q5-G)") (class "Default")
      (node (ref "Q5") (pin "4") (pinfunction "G_4") (pintype "passive"))
      (node (ref "R8") (pin "2") (pinfunction "2_2") (pintype "passive"))
    )
    (net (code "81") (name "Net-(Q6-D)") (class "Default")
      (node (ref "D6") (pin "A") (pinfunction "A_A") (pintype "passive"))
      (node (ref "Q6") (pin "MB") (pinfunction "D_MB") (pintype "passive"))
      (node (ref "X3") (pin "2") (pinfunction "S_2") (pintype "passive"))
    )
    (net (code "82") (name "Net-(Q6-G)") (class "Default")
      (node (ref "Q6") (pin "4") (pinfunction "G_4") (pintype "passive"))
      (node (ref "R10") (pin "2") (pinfunction "2_2") (pintype "passive"))
    )
    (net (code "83") (name "Net-(U$1-T+)") (class "Default")
      (node (ref "U$1") (pin "3") (pinfunction "T+_3") (pintype "bidirectional"))
      (node (ref "X2") (pin "7") (pinfunction "S_7") (pintype "passive"))
    )
    (net (code "84") (name "Net-(U$1-T-)") (class "Default")
      (node (ref "U$1") (pin "2") (pinfunction "T-_2") (pintype "bidirectional"))
      (node (ref "X2") (pin "8") (pinfunction "S_8") (pintype "passive"))
    )
    (net (code "85") (name "Net-(U$2-T+)") (class "Default")
      (node (ref "U$2") (pin "3") (pinfunction "T+_3") (pintype "bidirectional"))
      (node (ref "X2") (pin "5") (pinfunction "S_5") (pintype "passive"))
    )
    (net (code "86") (name "Net-(U$2-T-)") (class "Default")
      (node (ref "U$2") (pin "2") (pinfunction "T-_2") (pintype "bidirectional"))
      (node (ref "X2") (pin "6") (pinfunction "S_6") (pintype "passive"))
    )
    (net (code "87") (name "Net-(U$3-T+)") (class "Default")
      (node (ref "U$3") (pin "3") (pinfunction "T+_3") (pintype "bidirectional"))
      (node (ref "X2") (pin "3") (pinfunction "S_3") (pintype "passive"))
    )
    (net (code "88") (name "Net-(U$3-T-)") (class "Default")
      (node (ref "U$3") (pin "2") (pinfunction "T-_2") (pintype "bidirectional"))
      (node (ref "X2") (pin "4") (pinfunction "S_4") (pintype "passive"))
    )
    (net (code "89") (name "Net-(U$4-T+)") (class "Default")
      (node (ref "U$4") (pin "3") (pinfunction "T+_3") (pintype "bidirectional"))
      (node (ref "X2") (pin "1") (pinfunction "S_1") (pintype "passive"))
    )
    (net (code "90") (name "Net-(U$4-T-)") (class "Default")
      (node (ref "U$4") (pin "2") (pinfunction "T-_2") (pintype "bidirectional"))
      (node (ref "X2") (pin "2") (pinfunction "S_2") (pintype "passive"))
    )
    (net (code "91") (name "Net-(X1A-S)") (class "Default")
      (node (ref "R14") (pin "2") (pinfunction "2_2") (pintype "passive"))
      (node (ref "X1") (pin "1") (pinfunction "S_1") (pintype "passive"))
    )
    (net (code "92") (name "Net-(X1C-S)") (class "Default")
      (node (ref "R15") (pin "2") (pinfunction "2_2") (pintype "passive"))
      (node (ref "X1") (pin "3") (pinfunction "S_3") (pintype "passive"))
    )
    (net (code "93") (name "Net-(X1E-S)") (class "Default")
      (node (ref "R16") (pin "2") (pinfunction "2_2") (pintype "passive"))
      (node (ref "X1") (pin "5") (pinfunction "S_5") (pintype "passive"))
    )
    (net (code "94") (name "Net-(X1G-S)") (class "Default")
      (node (ref "R17") (pin "2") (pinfunction "2_2") (pintype "passive"))
      (node (ref "X1") (pin "7") (pinfunction "S_7") (pintype "passive"))
    )
    (net (code "95") (name "unconnected-(H1-MOUNT-PadB3,3)") (class "Default")
      (node (ref "H1") (pin "B3,3") (pinfunction "MOUNT_B3,3") (pintype "passive"))
    )
    (net (code "96") (name "unconnected-(H2-MOUNT-PadB3,3)") (class "Default")
      (node (ref "H2") (pin "B3,3") (pinfunction "MOUNT_B3,3") (pintype "passive"))
    )
    (net (code "97") (name "unconnected-(H3-MOUNT-PadB3,3)") (class "Default")
      (node (ref "H3") (pin "B3,3") (pinfunction "MOUNT_B3,3") (pintype "passive"))
    )
    (net (code "98") (name "unconnected-(H4-MOUNT-PadB3,3)") (class "Default")
      (node (ref "H4") (pin "B3,3") (pinfunction "MOUNT_B3,3") (pintype "passive"))
    )
    (net (code "99") (name "unconnected-(IC4-I1-Pad1)") (class "Default")
      (node (ref "IC4") (pin "1") (pinfunction "I1_1") (pintype "input"))
    )
    (net (code "100") (name "unconnected-(IC4-O1-Pad16)") (class "Default")
      (node (ref "IC4") (pin "16") (pinfunction "O1_16") (pintype "open_collector"))
    )
    (net (code "101") (name "unconnected-(J8-Pad1)") (class "Default")
      (node (ref "J8") (pin "1") (pinfunction "1_1") (pintype "bidirectional"))
    )
    (net (code "102") (name "unconnected-(J8-Pad2)") (class "Default")
      (node (ref "J8") (pin "2") (pinfunction "2_2") (pintype "bidirectional"))
    )
    (net (code "103") (name "unconnected-(J8-Pad3)") (class "Default")
      (node (ref "J8") (pin "3") (pinfunction "3_3") (pintype "bidirectional"))
    )
    (net (code "104") (name "unconnected-(J8-Pad4)") (class "Default")
      (node (ref "J8") (pin "4") (pinfunction "4_4") (pintype "bidirectional"))
    )
    (net (code "105") (name "unconnected-(J8-Pad5)") (class "Default")
      (node (ref "J8") (pin "5") (pinfunction "5_5") (pintype "bidirectional"))
    )
    (net (code "106") (name "unconnected-(J8-Pad6)") (class "Default")
      (node (ref "J8") (pin "6") (pinfunction "6_6") (pintype "bidirectional"))
    )
    (net (code "107") (name "unconnected-(J8-Pad7)") (class "Default")
      (node (ref "J8") (pin "7") (pinfunction "7_7") (pintype "bidirectional"))
    )
    (net (code "108") (name "unconnected-(J8-Pad8)") (class "Default")
      (node (ref "J8") (pin "8") (pinfunction "8_8") (pintype "bidirectional"))
    )
    (net (code "109") (name "unconnected-(J8-Pad9)") (class "Default")
      (node (ref "J8") (pin "9") (pinfunction "9_9") (pintype "bidirectional"))
    )
    (net (code "110") (name "unconnected-(J8-Pad10)") (class "Default")
      (node (ref "J8") (pin "10") (pinfunction "10_10") (pintype "bidirectional"))
    )
    (net (code "111") (name "unconnected-(J8-Pad11)") (class "Default")
      (node (ref "J8") (pin "11") (pinfunction "11_11") (pintype "bidirectional"))
    )
    (net (code "112") (name "unconnected-(J8-Pad12)") (class "Default")
      (node (ref "J8") (pin "12") (pinfunction "12_12") (pintype "bidirectional"))
    )
    (net (code "113") (name "unconnected-(J8-Pad13)") (class "Default")
      (node (ref "J8") (pin "13") (pinfunction "13_13") (pintype "bidirectional"))
    )
    (net (code "114") (name "unconnected-(J8-Pad14)") (class "Default")
      (node (ref "J8") (pin "14") (pinfunction "14_14") (pintype "bidirectional"))
    )
    (net (code "115") (name "unconnected-(J8-Pad15)") (class "Default")
      (node (ref "J8") (pin "15") (pinfunction "15_15") (pintype "bidirectional"))
    )
    (net (code "116") (name "unconnected-(J8-Pad16)") (class "Default")
      (node (ref "J8") (pin "16") (pinfunction "16_16") (pintype "bidirectional"))
    )
  )
)
